# Sheet1.net
KiCad netlist of a schematic drawn in Altium Designer
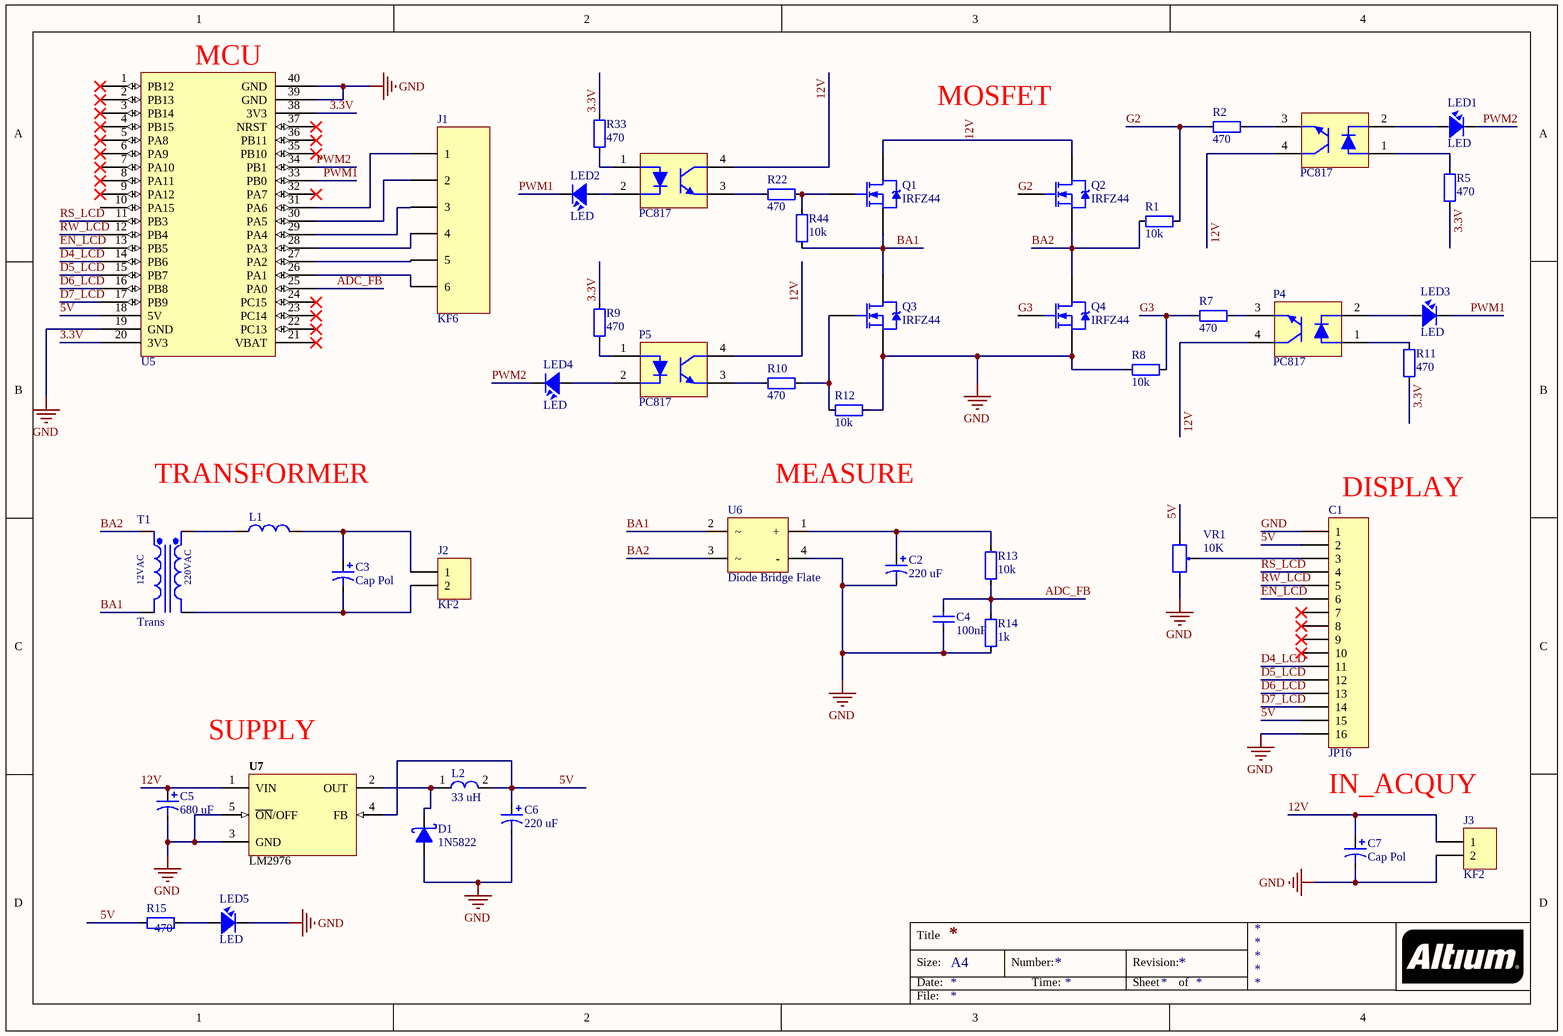
[diagram p0: Sheet1.SchDoc]

(export (version "E")
  (design (tool "Eeschema 10.0.6"))
  (components
    (comp (ref "C1")
      (value "JP16")
      (footprint "JP16-C1T")
      (description "WR-PHD 2.54 mm Angled Socket Header")
      (fields
        (field (name "MANUFACTURER") "Würth Elektronik eiSos GmbH")
        (field (name "PARTNO") "613016143121")
        (field (name "CREATED BY") "Karrer Zheng")
      )
      (libsource (lib "My Library") (part "JP16"))
    )
    (comp (ref "C2")
      (value "220 uF")
      (footprint "C8mm")
      (description "Polarized Capacitor (Axial)")
      (fields (field (name "PUBLISHER") "Altium Limited"))
      (libsource (lib "My Library") (part "Cap Pol"))
    )
    (comp (ref "C3")
      (value "Cap Pol")
      (footprint "C12mm")
      (description "Polarized Capacitor (Axial)")
      (fields (field (name "PUBLISHER") "Altium Limited"))
      (libsource (lib "My Library") (part "Cap Pol"))
    )
    (comp (ref "C4")
      (value "100nF")
      (footprint "CAP_0805")
      (description "Capacitor")
      (fields (field (name "PUBLISHER") "Altium Limited"))
      (libsource (lib "My Library") (part "CapSMD"))
    )
    (comp (ref "C5")
      (value "680 uF")
      (footprint "C12mm")
      (description "Polarized Capacitor (Axial)")
      (fields (field (name "PUBLISHER") "Altium Limited"))
      (libsource (lib "My Library") (part "Cap Pol"))
    )
    (comp (ref "C6")
      (value "220 uF")
      (footprint "C8mm")
      (description "Polarized Capacitor (Axial)")
      (fields (field (name "PUBLISHER") "Altium Limited"))
      (libsource (lib "My Library") (part "Cap Pol"))
    )
    (comp (ref "C7")
      (value "Cap Pol")
      (footprint "C12mm")
      (description "Polarized Capacitor (Axial)")
      (fields (field (name "PUBLISHER") "Altium Limited"))
      (libsource (lib "My Library") (part "Cap Pol"))
    )
    (comp (ref "D1")
      (value "1N5822")
      (footprint "DIO-SMD-123")
      (description "Schottky Rectifiers")
      (libsource (lib "My Library") (part "1N5822"))
    )
    (comp (ref "J1")
      (value "KF6")
      (footprint "KF6-5")
      (fields
        (field (name "MANUFACTURER") "Würth Elektronik eiSos GmbH")
        (field (name "PARTNO") "691133710006")
        (field (name "CREATED BY") "Baojun Chen")
      )
      (libsource (lib "My Library") (part "KF6"))
    )
    (comp (ref "J2")
      (value "KF2")
      (footprint "KF2-5.08")
      (fields
        (field (name "MANUFACTURER") "Würth Elektronik eiSos GmbH")
        (field (name "PARTNO") "691103110002")
        (field (name "CREATED BY") "Karrer Zheng")
      )
      (libsource (lib "My Library") (part "KF2"))
    )
    (comp (ref "J3")
      (value "KF2")
      (footprint "KF2-5.08")
      (fields
        (field (name "MANUFACTURER") "Würth Elektronik eiSos GmbH")
        (field (name "PARTNO") "691103110002")
        (field (name "CREATED BY") "Karrer Zheng")
      )
      (libsource (lib "My Library") (part "KF2"))
    )
    (comp (ref "L1")
      (value "150mH")
      (footprint "L01")
      (description "Inductor")
      (libsource (lib "My Library") (part "L1"))
    )
    (comp (ref "L2")
      (value "33 uH")
      (footprint "L-SMD-M-7.3x4.5")
      (fields
        (field (name "PARTNO") "78477010")
        (field (name "MANUFACTURER") "Wurth Elektronik")
        (field (name "CREATED BY") "Baojun Chen")
      )
      (libsource (lib "My Library") (part "L-SMD-1"))
    )
    (comp (ref "LED1")
      (value "LED")
      (footprint "LED-1206-Red")
      (description "LED Single colour Green and Red")
      (libsource (lib "My Library") (part "LED"))
    )
    (comp (ref "LED2")
      (value "LED")
      (footprint "LED-1206-Red")
      (description "LED Single colour Green and Red")
      (libsource (lib "My Library") (part "LED"))
    )
    (comp (ref "LED3")
      (value "LED")
      (footprint "LED-1206-Red")
      (description "LED Single colour Green and Red")
      (libsource (lib "My Library") (part "LED"))
    )
    (comp (ref "LED4")
      (value "LED")
      (footprint "LED-1206-Red")
      (description "LED Single colour Green and Red")
      (libsource (lib "My Library") (part "LED"))
    )
    (comp (ref "LED5")
      (value "LED")
      (footprint "LED-1206-Red")
      (description "LED Single colour Green and Red")
      (libsource (lib "My Library") (part "LED"))
    )
    (comp (ref "P1")
      (value "PC817")
      (footprint "DIP-4")
      (description "NPN PHOTO General Purpose Amplifier")
      (fields (field (name "PUBLISHER") "Altium Limited"))
      (libsource (lib "") (part "PC817_1"))
    )
    (comp (ref "P3")
      (value "PC817")
      (footprint "DIP-4")
      (description "NPN PHOTO General Purpose Amplifier")
      (fields (field (name "PUBLISHER") "Altium Limited"))
      (libsource (lib "Devzone_SCHLib") (part "PC817"))
    )
    (comp (ref "P4")
      (value "PC817")
      (footprint "DIP-4")
      (description "NPN PHOTO General Purpose Amplifier")
      (fields (field (name "PUBLISHER") "Altium Limited"))
      (libsource (lib "") (part "PC817_1"))
    )
    (comp (ref "P5")
      (value "PC817")
      (footprint "DIP-4")
      (description "NPN PHOTO General Purpose Amplifier")
      (fields (field (name "PUBLISHER") "Altium Limited"))
      (libsource (lib "Devzone_SCHLib") (part "PC817"))
    )
    (comp (ref "Q1")
      (value "IRFZ44")
      (footprint "TO-220-Heatsink")
      (libsource (lib "My Library") (part "IRFZ44"))
    )
    (comp (ref "Q2")
      (value "IRFZ44")
      (footprint "TO-220-Heatsink")
      (libsource (lib "My Library") (part "IRFZ44"))
    )
    (comp (ref "Q3")
      (value "IRFZ44")
      (footprint "TO-220-Heatsink")
      (libsource (lib "My Library") (part "IRFZ44"))
    )
    (comp (ref "Q4")
      (value "IRFZ44")
      (footprint "TO-220-Heatsink")
      (libsource (lib "My Library") (part "IRFZ44"))
    )
    (comp (ref "R1")
      (value "10k")
      (footprint "RES-SMD-0805")
      (description "Resistor")
      (fields
        (field (name "MANUFACTURER") "Generic Components")
        (field (name "PUBLISHER") "Altium Hobart Technology Centre")
      )
      (libsource (lib "My Library") (part "Resistor - SMD"))
    )
    (comp (ref "R2")
      (value "470")
      (footprint "RES-SMD-0805")
      (description "Resistor")
      (fields
        (field (name "MANUFACTURER") "Generic Components")
        (field (name "PUBLISHER") "Altium Hobart Technology Centre")
      )
      (libsource (lib "My Library") (part "Resistor - SMD"))
    )
    (comp (ref "R5")
      (value "470")
      (footprint "RES-SMD-0805")
      (description "Resistor")
      (fields
        (field (name "MANUFACTURER") "Generic Components")
        (field (name "PUBLISHER") "Altium Hobart Technology Centre")
      )
      (libsource (lib "My Library") (part "Resistor - SMD"))
    )
    (comp (ref "R7")
      (value "470")
      (footprint "RES-SMD-0805")
      (description "Resistor")
      (fields
        (field (name "MANUFACTURER") "Generic Components")
        (field (name "PUBLISHER") "Altium Hobart Technology Centre")
      )
      (libsource (lib "My Library") (part "Resistor - SMD"))
    )
    (comp (ref "R8")
      (value "10k")
      (footprint "RES-SMD-0805")
      (description "Resistor")
      (fields
        (field (name "MANUFACTURER") "Generic Components")
        (field (name "PUBLISHER") "Altium Hobart Technology Centre")
      )
      (libsource (lib "My Library") (part "Resistor - SMD"))
    )
    (comp (ref "R9")
      (value "470")
      (footprint "RES-SMD-0805")
      (description "Resistor")
      (fields
        (field (name "MANUFACTURER") "Generic Components")
        (field (name "PUBLISHER") "Altium Hobart Technology Centre")
      )
      (libsource (lib "My Library") (part "Resistor - SMD"))
    )
    (comp (ref "R10")
      (value "470")
      (footprint "RES-SMD-0805")
      (description "Resistor")
      (fields
        (field (name "MANUFACTURER") "Generic Components")
        (field (name "PUBLISHER") "Altium Hobart Technology Centre")
      )
      (libsource (lib "My Library") (part "Resistor - SMD"))
    )
    (comp (ref "R11")
      (value "470")
      (footprint "RES-SMD-0805")
      (description "Resistor")
      (fields
        (field (name "MANUFACTURER") "Generic Components")
        (field (name "PUBLISHER") "Altium Hobart Technology Centre")
      )
      (libsource (lib "My Library") (part "Resistor - SMD"))
    )
    (comp (ref "R12")
      (value "10k")
      (footprint "RES-SMD-0805")
      (description "Resistor")
      (fields
        (field (name "MANUFACTURER") "Generic Components")
        (field (name "PUBLISHER") "Altium Hobart Technology Centre")
      )
      (libsource (lib "My Library") (part "Resistor - SMD"))
    )
    (comp (ref "R13")
      (value "10k")
      (footprint "RES-SMD-0805")
      (description "Resistor")
      (fields
        (field (name "MANUFACTURER") "Generic Components")
        (field (name "PUBLISHER") "Altium Hobart Technology Centre")
      )
      (libsource (lib "My Library") (part "Resistor - SMD"))
    )
    (comp (ref "R14")
      (value "1k")
      (footprint "RES-SMD-0805")
      (description "Resistor")
      (fields
        (field (name "MANUFACTURER") "Generic Components")
        (field (name "PUBLISHER") "Altium Hobart Technology Centre")
      )
      (libsource (lib "My Library") (part "Resistor - SMD"))
    )
    (comp (ref "R15")
      (value "470")
      (footprint "RES-SMD-0805")
      (description "Resistor")
      (fields
        (field (name "MANUFACTURER") "Generic Components")
        (field (name "PUBLISHER") "Altium Hobart Technology Centre")
      )
      (libsource (lib "My Library") (part "Resistor - SMD"))
    )
    (comp (ref "R22")
      (value "470")
      (footprint "RES-SMD-0805")
      (description "Resistor")
      (fields
        (field (name "MANUFACTURER") "Generic Components")
        (field (name "PUBLISHER") "Altium Hobart Technology Centre")
      )
      (libsource (lib "My Library") (part "Resistor - SMD"))
    )
    (comp (ref "R33")
      (value "470")
      (footprint "RES-SMD-0805")
      (description "Resistor")
      (fields
        (field (name "MANUFACTURER") "Generic Components")
        (field (name "PUBLISHER") "Altium Hobart Technology Centre")
      )
      (libsource (lib "My Library") (part "Resistor - SMD"))
    )
    (comp (ref "R44")
      (value "10k")
      (footprint "RES-SMD-0805")
      (description "Resistor")
      (fields
        (field (name "MANUFACTURER") "Generic Components")
        (field (name "PUBLISHER") "Altium Hobart Technology Centre")
      )
      (libsource (lib "My Library") (part "Resistor - SMD"))
    )
    (comp (ref "T1")
      (value "Trans")
      (footprint "Transformer 12V-6VA")
      (description "Transformer (12V-6VA)")
      (fields (field (name "PUBLISHER") "Altium Limited"))
      (libsource (lib "My Library") (part "Trans"))
    )
    (comp (ref "U5")
      (value "STM32 BluePill")
      (footprint "STM32 Bluepill")
      (description "STM32F103C8T6 breakout board")
      (libsource (lib "My Library") (part "STM32 BluePill"))
    )
    (comp (ref "U6")
      (value "Diode Bridge Flate")
      (footprint "DB207S")
      (description "Diode Bridge")
      (libsource (lib "My Library") (part "Diode Bridge Flate"))
    )
    (comp (ref "U7") (value "LM2976") (footprint "TO-263") (libsource (lib "My Library") (part "LM2596")))
    (comp (ref "VR1")
      (value "10K")
      (footprint "VR")
      (description "Var Resistor")
      (libsource (lib "My Library") (part "VR"))
    )
  )
  (nets
    (net (code "1") (name "/3.3V") (class "Default")
      (node (ref "R11") (pin "2") (pinfunction "2_2") (pintype "passive"))
      (node (ref "R33") (pin "2") (pinfunction "2_2") (pintype "passive"))
      (node (ref "R5") (pin "2") (pinfunction "2_2") (pintype "passive"))
      (node (ref "R9") (pin "2") (pinfunction "2_2") (pintype "passive"))
      (node (ref "U5") (pin "20") (pinfunction "3V3_20") (pintype "power_in"))
      (node (ref "U5") (pin "38") (pinfunction "3V3_38") (pintype "power_in"))
    )
    (net (code "2") (name "/5V") (class "Default")
      (node (ref "C1") (pin "15") (pinfunction "15_15") (pintype "passive"))
      (node (ref "C1") (pin "2") (pinfunction "2_2") (pintype "passive"))
      (node (ref "C6") (pin "1") (pinfunction "1_1") (pintype "passive"))
      (node (ref "L2") (pin "2") (pinfunction "2_2") (pintype "passive"))
      (node (ref "R15") (pin "1") (pinfunction "1_1") (pintype "passive"))
      (node (ref "U5") (pin "18") (pinfunction "5V_18") (pintype "power_in"))
      (node (ref "U7") (pin "4") (pinfunction "FB_4") (pintype "input"))
      (node (ref "VR1") (pin "1") (pinfunction "1_1") (pintype "passive"))
    )
    (net (code "3") (name "/12V") (class "Default")
      (node (ref "C5") (pin "1") (pinfunction "1_1") (pintype "passive"))
      (node (ref "C7") (pin "1") (pinfunction "1_1") (pintype "passive"))
      (node (ref "J3") (pin "1") (pinfunction "1_1") (pintype "passive"))
      (node (ref "P1") (pin "4") (pinfunction "4_4") (pintype "passive"))
      (node (ref "P3") (pin "4") (pinfunction "4_4") (pintype "passive"))
      (node (ref "P4") (pin "4") (pinfunction "4_4") (pintype "passive"))
      (node (ref "P5") (pin "4") (pinfunction "4_4") (pintype "passive"))
      (node (ref "Q1") (pin "2") (pinfunction "D_2") (pintype "passive"))
      (node (ref "Q2") (pin "2") (pinfunction "D_2") (pintype "passive"))
      (node (ref "U7") (pin "1") (pinfunction "VIN_1") (pintype "power_in"))
    )
    (net (code "4") (name "/ADC_FB") (class "Default")
      (node (ref "C4") (pin "2") (pinfunction "2_2") (pintype "passive"))
      (node (ref "R13") (pin "2") (pinfunction "2_2") (pintype "passive"))
      (node (ref "R14") (pin "1") (pinfunction "1_1") (pintype "passive"))
      (node (ref "U5") (pin "25") (pinfunction "PA0_25") (pintype "bidirectional"))
    )
    (net (code "5") (name "/BA1") (class "Default")
      (node (ref "Q1") (pin "3") (pinfunction "S_3") (pintype "passive"))
      (node (ref "Q3") (pin "2") (pinfunction "D_2") (pintype "passive"))
      (node (ref "R44") (pin "1") (pinfunction "1_1") (pintype "passive"))
      (node (ref "T1") (pin "2") (pinfunction "Pri-_2") (pintype "passive"))
      (node (ref "U6") (pin "2") (pinfunction "~_2") (pintype "passive"))
    )
    (net (code "6") (name "/BA2") (class "Default")
      (node (ref "Q2") (pin "3") (pinfunction "S_3") (pintype "passive"))
      (node (ref "Q4") (pin "2") (pinfunction "D_2") (pintype "passive"))
      (node (ref "R1") (pin "1") (pinfunction "1_1") (pintype "passive"))
      (node (ref "T1") (pin "1") (pinfunction "Pri+_1") (pintype "passive"))
      (node (ref "U6") (pin "3") (pinfunction "~_3") (pintype "passive"))
    )
    (net (code "7") (name "/D4_LCD") (class "Default")
      (node (ref "C1") (pin "11") (pinfunction "11_11") (pintype "passive"))
      (node (ref "U5") (pin "14") (pinfunction "PB6_14") (pintype "bidirectional"))
    )
    (net (code "8") (name "/D5_LCD") (class "Default")
      (node (ref "C1") (pin "12") (pinfunction "12_12") (pintype "passive"))
      (node (ref "U5") (pin "15") (pinfunction "PB7_15") (pintype "bidirectional"))
    )
    (net (code "9") (name "/D6_LCD") (class "Default")
      (node (ref "C1") (pin "13") (pinfunction "13_13") (pintype "passive"))
      (node (ref "U5") (pin "16") (pinfunction "PB8_16") (pintype "bidirectional"))
    )
    (net (code "10") (name "/D7_LCD") (class "Default")
      (node (ref "C1") (pin "14") (pinfunction "14_14") (pintype "passive"))
      (node (ref "U5") (pin "17") (pinfunction "PB9_17") (pintype "bidirectional"))
    )
    (net (code "11") (name "/EN_LCD") (class "Default")
      (node (ref "C1") (pin "6") (pinfunction "6_6") (pintype "passive"))
      (node (ref "U5") (pin "13") (pinfunction "PB5_13") (pintype "bidirectional"))
    )
    (net (code "12") (name "/G2") (class "Default")
      (node (ref "Q2") (pin "1") (pinfunction "G_1") (pintype "passive"))
      (node (ref "R1") (pin "2") (pinfunction "2_2") (pintype "passive"))
      (node (ref "R2") (pin "1") (pinfunction "1_1") (pintype "passive"))
    )
    (net (code "13") (name "/G3") (class "Default")
      (node (ref "Q4") (pin "1") (pinfunction "G_1") (pintype "passive"))
      (node (ref "R7") (pin "2") (pinfunction "2_2") (pintype "passive"))
      (node (ref "R8") (pin "1") (pinfunction "1_1") (pintype "passive"))
    )
    (net (code "14") (name "/PWM1") (class "Default")
      (node (ref "LED2") (pin "2") (pinfunction "2_2") (pintype "passive"))
      (node (ref "LED3") (pin "2") (pinfunction "2_2") (pintype "passive"))
      (node (ref "U5") (pin "33") (pinfunction "PB0_33") (pintype "bidirectional"))
    )
    (net (code "15") (name "/PWM2") (class "Default")
      (node (ref "LED1") (pin "2") (pinfunction "2_2") (pintype "passive"))
      (node (ref "LED4") (pin "2") (pinfunction "2_2") (pintype "passive"))
      (node (ref "U5") (pin "34") (pinfunction "PB1_34") (pintype "bidirectional"))
    )
    (net (code "16") (name "/RS_LCD") (class "Default")
      (node (ref "C1") (pin "4") (pinfunction "4_4") (pintype "passive"))
      (node (ref "U5") (pin "11") (pinfunction "PB3_11") (pintype "bidirectional"))
    )
    (net (code "17") (name "/RW_LCD") (class "Default")
      (node (ref "C1") (pin "5") (pinfunction "5_5") (pintype "passive"))
      (node (ref "U5") (pin "12") (pinfunction "PB4_12") (pintype "bidirectional"))
    )
    (net (code "18") (name "GND") (class "Default")
      (node (ref "C1") (pin "1") (pinfunction "1_1") (pintype "passive"))
      (node (ref "C1") (pin "16") (pinfunction "16_16") (pintype "passive"))
      (node (ref "C2") (pin "2") (pinfunction "2_2") (pintype "passive"))
      (node (ref "C4") (pin "1") (pinfunction "1_1") (pintype "passive"))
      (node (ref "C5") (pin "2") (pinfunction "2_2") (pintype "passive"))
      (node (ref "C6") (pin "2") (pinfunction "2_2") (pintype "passive"))
      (node (ref "C7") (pin "2") (pinfunction "2_2") (pintype "passive"))
      (node (ref "D1") (pin "1") (pinfunction "A_1") (pintype "passive"))
      (node (ref "J3") (pin "2") (pinfunction "2_2") (pintype "passive"))
      (node (ref "LED5") (pin "2") (pinfunction "2_2") (pintype "passive"))
      (node (ref "Q3") (pin "3") (pinfunction "S_3") (pintype "passive"))
      (node (ref "Q4") (pin "3") (pinfunction "S_3") (pintype "passive"))
      (node (ref "R12") (pin "1") (pinfunction "1_1") (pintype "passive"))
      (node (ref "R14") (pin "2") (pinfunction "2_2") (pintype "passive"))
      (node (ref "R8") (pin "2") (pinfunction "2_2") (pintype "passive"))
      (node (ref "U5") (pin "19") (pinfunction "GND_19") (pintype "power_in"))
      (node (ref "U5") (pin "39") (pinfunction "GND_39") (pintype "power_in"))
      (node (ref "U5") (pin "40") (pinfunction "GND_40") (pintype "power_in"))
      (node (ref "U6") (pin "4") (pinfunction "-_4") (pintype "passive"))
      (node (ref "U7") (pin "3") (pinfunction "GND_3") (pintype "power_in"))
      (node (ref "U7") (pin "5") (pinfunction "~{ON}/OFF_5") (pintype "input"))
      (node (ref "VR1") (pin "3") (pinfunction "3_3") (pintype "passive"))
    )
    (net (code "19") (name "Net-(C1-Pad3)") (class "Default")
      (node (ref "C1") (pin "3") (pinfunction "3_3") (pintype "passive"))
      (node (ref "VR1") (pin "2") (pinfunction "2_2") (pintype "passive"))
    )
    (net (code "20") (name "Net-(C3-Pad1)") (class "Default")
      (node (ref "C3") (pin "1") (pinfunction "1_1") (pintype "passive"))
      (node (ref "J2") (pin "1") (pinfunction "1_1") (pintype "passive"))
      (node (ref "L1") (pin "2") (pinfunction "2_2") (pintype "passive"))
    )
    (net (code "21") (name "Net-(D1-K)") (class "Default")
      (node (ref "D1") (pin "2") (pinfunction "K_2") (pintype "passive"))
      (node (ref "L2") (pin "1") (pinfunction "1_1") (pintype "passive"))
      (node (ref "U7") (pin "2") (pinfunction "OUT_2") (pintype "power_in"))
    )
    (net (code "22") (name "Net-(LED1-Pad1)") (class "Default")
      (node (ref "LED1") (pin "1") (pinfunction "1_1") (pintype "passive"))
      (node (ref "P1") (pin "2") (pinfunction "2_2") (pintype "passive"))
    )
    (net (code "23") (name "Net-(LED2-Pad1)") (class "Default")
      (node (ref "LED2") (pin "1") (pinfunction "1_1") (pintype "passive"))
      (node (ref "P3") (pin "2") (pinfunction "2_2") (pintype "passive"))
    )
    (net (code "24") (name "Net-(LED3-Pad1)") (class "Default")
      (node (ref "LED3") (pin "1") (pinfunction "1_1") (pintype "passive"))
      (node (ref "P4") (pin "2") (pinfunction "2_2") (pintype "passive"))
    )
    (net (code "25") (name "Net-(LED4-Pad1)") (class "Default")
      (node (ref "LED4") (pin "1") (pinfunction "1_1") (pintype "passive"))
      (node (ref "P5") (pin "2") (pinfunction "2_2") (pintype "passive"))
    )
    (net (code "26") (name "Net-(LED5-Pad1)") (class "Default")
      (node (ref "LED5") (pin "1") (pinfunction "1_1") (pintype "passive"))
      (node (ref "R15") (pin "2") (pinfunction "2_2") (pintype "passive"))
    )
    (net (code "27") (name "Net-(P1-Pad1)") (class "Default")
      (node (ref "P1") (pin "1") (pinfunction "1_1") (pintype "passive"))
      (node (ref "R5") (pin "1") (pinfunction "1_1") (pintype "passive"))
    )
    (net (code "28") (name "Net-(P1-Pad3)") (class "Default")
      (node (ref "P1") (pin "3") (pinfunction "3_3") (pintype "passive"))
      (node (ref "R2") (pin "2") (pinfunction "2_2") (pintype "passive"))
    )
    (net (code "29") (name "Net-(P3-Pad1)") (class "Default")
      (node (ref "P3") (pin "1") (pinfunction "1_1") (pintype "passive"))
      (node (ref "R33") (pin "1") (pinfunction "1_1") (pintype "passive"))
    )
    (net (code "30") (name "Net-(P3-Pad3)") (class "Default")
      (node (ref "P3") (pin "3") (pinfunction "3_3") (pintype "passive"))
      (node (ref "R22") (pin "1") (pinfunction "1_1") (pintype "passive"))
    )
    (net (code "31") (name "Net-(P4-Pad1)") (class "Default")
      (node (ref "P4") (pin "1") (pinfunction "1_1") (pintype "passive"))
      (node (ref "R11") (pin "1") (pinfunction "1_1") (pintype "passive"))
    )
    (net (code "32") (name "Net-(P4-Pad3)") (class "Default")
      (node (ref "P4") (pin "3") (pinfunction "3_3") (pintype "passive"))
      (node (ref "R7") (pin "1") (pinfunction "1_1") (pintype "passive"))
    )
    (net (code "33") (name "Net-(P5-Pad1)") (class "Default")
      (node (ref "P5") (pin "1") (pinfunction "1_1") (pintype "passive"))
      (node (ref "R9") (pin "1") (pinfunction "1_1") (pintype "passive"))
    )
    (net (code "34") (name "Net-(P5-Pad3)") (class "Default")
      (node (ref "P5") (pin "3") (pinfunction "3_3") (pintype "passive"))
      (node (ref "R10") (pin "2") (pinfunction "2_2") (pintype "passive"))
    )
    (net (code "35") (name "Net-(Q1-G)") (class "Default")
      (node (ref "Q1") (pin "1") (pinfunction "G_1") (pintype "passive"))
      (node (ref "R22") (pin "2") (pinfunction "2_2") (pintype "passive"))
      (node (ref "R44") (pin "2") (pinfunction "2_2") (pintype "passive"))
    )
    (net (code "36") (name "Net-(Q3-G)") (class "Default")
      (node (ref "Q3") (pin "1") (pinfunction "G_1") (pintype "passive"))
      (node (ref "R10") (pin "1") (pinfunction "1_1") (pintype "passive"))
      (node (ref "R12") (pin "2") (pinfunction "2_2") (pintype "passive"))
    )
    (net (code "37") (name "Net-(T1-Sec+)") (class "Default")
      (node (ref "L1") (pin "1") (pinfunction "1_1") (pintype "passive"))
      (node (ref "T1") (pin "3") (pinfunction "Sec+_3") (pintype "passive"))
    )
    (net (code "38") (name "Net-(T1-Sec-)") (class "Default")
      (node (ref "C3") (pin "2") (pinfunction "2_2") (pintype "passive"))
      (node (ref "J2") (pin "2") (pinfunction "2_2") (pintype "passive"))
      (node (ref "T1") (pin "4") (pinfunction "Sec-_4") (pintype "passive"))
    )
    (net (code "39") (name "Net-(U5-PA1)") (class "Default")
      (node (ref "J1") (pin "6") (pinfunction "6_6") (pintype "passive"))
      (node (ref "U5") (pin "26") (pinfunction "PA1_26") (pintype "bidirectional"))
    )
    (net (code "40") (name "Net-(U5-PA2)") (class "Default")
      (node (ref "J1") (pin "5") (pinfunction "5_5") (pintype "passive"))
      (node (ref "U5") (pin "27") (pinfunction "PA2_27") (pintype "bidirectional"))
    )
    (net (code "41") (name "Net-(U5-PA3)") (class "Default")
      (node (ref "J1") (pin "4") (pinfunction "4_4") (pintype "passive"))
      (node (ref "U5") (pin "28") (pinfunction "PA3_28") (pintype "bidirectional"))
    )
    (net (code "42") (name "Net-(U5-PA4)") (class "Default")
      (node (ref "J1") (pin "3") (pinfunction "3_3") (pintype "passive"))
      (node (ref "U5") (pin "29") (pinfunction "PA4_29") (pintype "bidirectional"))
    )
    (net (code "43") (name "Net-(U5-PA5)") (class "Default")
      (node (ref "J1") (pin "2") (pinfunction "2_2") (pintype "passive"))
      (node (ref "U5") (pin "30") (pinfunction "PA5_30") (pintype "bidirectional"))
    )
    (net (code "44") (name "Net-(U5-PA6)") (class "Default")
      (node (ref "J1") (pin "1") (pinfunction "1_1") (pintype "passive"))
      (node (ref "U5") (pin "31") (pinfunction "PA6_31") (pintype "bidirectional"))
    )
    (net (code "45") (name "Net-(U6-+)") (class "Default")
      (node (ref "C2") (pin "1") (pinfunction "1_1") (pintype "passive"))
      (node (ref "R13") (pin "1") (pinfunction "1_1") (pintype "passive"))
      (node (ref "U6") (pin "1") (pinfunction "+_1") (pintype "passive"))
    )
    (net (code "46") (name "unconnected-(C1-Pad7)") (class "Default")
      (node (ref "C1") (pin "7") (pinfunction "7_7") (pintype "passive+no_connect"))
    )
    (net (code "47") (name "unconnected-(C1-Pad8)") (class "Default")
      (node (ref "C1") (pin "8") (pinfunction "8_8") (pintype "passive+no_connect"))
    )
    (net (code "48") (name "unconnected-(C1-Pad9)") (class "Default")
      (node (ref "C1") (pin "9") (pinfunction "9_9") (pintype "passive+no_connect"))
    )
    (net (code "49") (name "unconnected-(C1-Pad10)") (class "Default")
      (node (ref "C1") (pin "10") (pinfunction "10_10") (pintype "passive+no_connect"))
    )
    (net (code "50") (name "unconnected-(U5-NRST-Pad37)") (class "Default")
      (node (ref "U5") (pin "37") (pinfunction "NRST_37") (pintype "bidirectional+no_connect"))
    )
    (net (code "51") (name "unconnected-(U5-PA7-Pad32)") (class "Default")
      (node (ref "U5") (pin "32") (pinfunction "PA7_32") (pintype "bidirectional+no_connect"))
    )
    (net (code "52") (name "unconnected-(U5-PA8-Pad5)") (class "Default")
      (node (ref "U5") (pin "5") (pinfunction "PA8_5") (pintype "bidirectional+no_connect"))
    )
    (net (code "53") (name "unconnected-(U5-PA9-Pad6)") (class "Default")
      (node (ref "U5") (pin "6") (pinfunction "PA9_6") (pintype "bidirectional+no_connect"))
    )
    (net (code "54") (name "unconnected-(U5-PA10-Pad7)") (class "Default")
      (node (ref "U5") (pin "7") (pinfunction "PA10_7") (pintype "bidirectional+no_connect"))
    )
    (net (code "55") (name "unconnected-(U5-PA11-Pad8)") (class "Default")
      (node (ref "U5") (pin "8") (pinfunction "PA11_8") (pintype "bidirectional+no_connect"))
    )
    (net (code "56") (name "unconnected-(U5-PA12-Pad9)") (class "Default")
      (node (ref "U5") (pin "9") (pinfunction "PA12_9") (pintype "bidirectional+no_connect"))
    )
    (net (code "57") (name "unconnected-(U5-PA15-Pad10)") (class "Default")
      (node (ref "U5") (pin "10") (pinfunction "PA15_10") (pintype "bidirectional"))
    )
    (net (code "58") (name "unconnected-(U5-PB10-Pad35)") (class "Default")
      (node (ref "U5") (pin "35") (pinfunction "PB10_35") (pintype "bidirectional+no_connect"))
    )
    (net (code "59") (name "unconnected-(U5-PB11-Pad36)") (class "Default")
      (node (ref "U5") (pin "36") (pinfunction "PB11_36") (pintype "bidirectional+no_connect"))
    )
    (net (code "60") (name "unconnected-(U5-PB12-Pad1)") (class "Default")
      (node (ref "U5") (pin "1") (pinfunction "PB12_1") (pintype "bidirectional+no_connect"))
    )
    (net (code "61") (name "unconnected-(U5-PB13-Pad2)") (class "Default")
      (node (ref "U5") (pin "2") (pinfunction "PB13_2") (pintype "bidirectional+no_connect"))
    )
    (net (code "62") (name "unconnected-(U5-PB14-Pad3)") (class "Default")
      (node (ref "U5") (pin "3") (pinfunction "PB14_3") (pintype "bidirectional+no_connect"))
    )
    (net (code "63") (name "unconnected-(U5-PB15-Pad4)") (class "Default")
      (node (ref "U5") (pin "4") (pinfunction "PB15_4") (pintype "bidirectional+no_connect"))
    )
    (net (code "64") (name "unconnected-(U5-PC13-Pad22)") (class "Default")
      (node (ref "U5") (pin "22") (pinfunction "PC13_22") (pintype "bidirectional+no_connect"))
    )
    (net (code "65") (name "unconnected-(U5-PC14-Pad23)") (class "Default")
      (node (ref "U5") (pin "23") (pinfunction "PC14_23") (pintype "bidirectional+no_connect"))
    )
    (net (code "66") (name "unconnected-(U5-PC15-Pad24)") (class "Default")
      (node (ref "U5") (pin "24") (pinfunction "PC15_24") (pintype "bidirectional+no_connect"))
    )
    (net (code "67") (name "unconnected-(U5-VBAT-Pad21)") (class "Default")
      (node (ref "U5") (pin "21") (pinfunction "VBAT_21") (pintype "power_in+no_connect"))
    )
  )
)
